# main_16_yobi.net
KiCad netlist of a schematic drawn in EAGLE
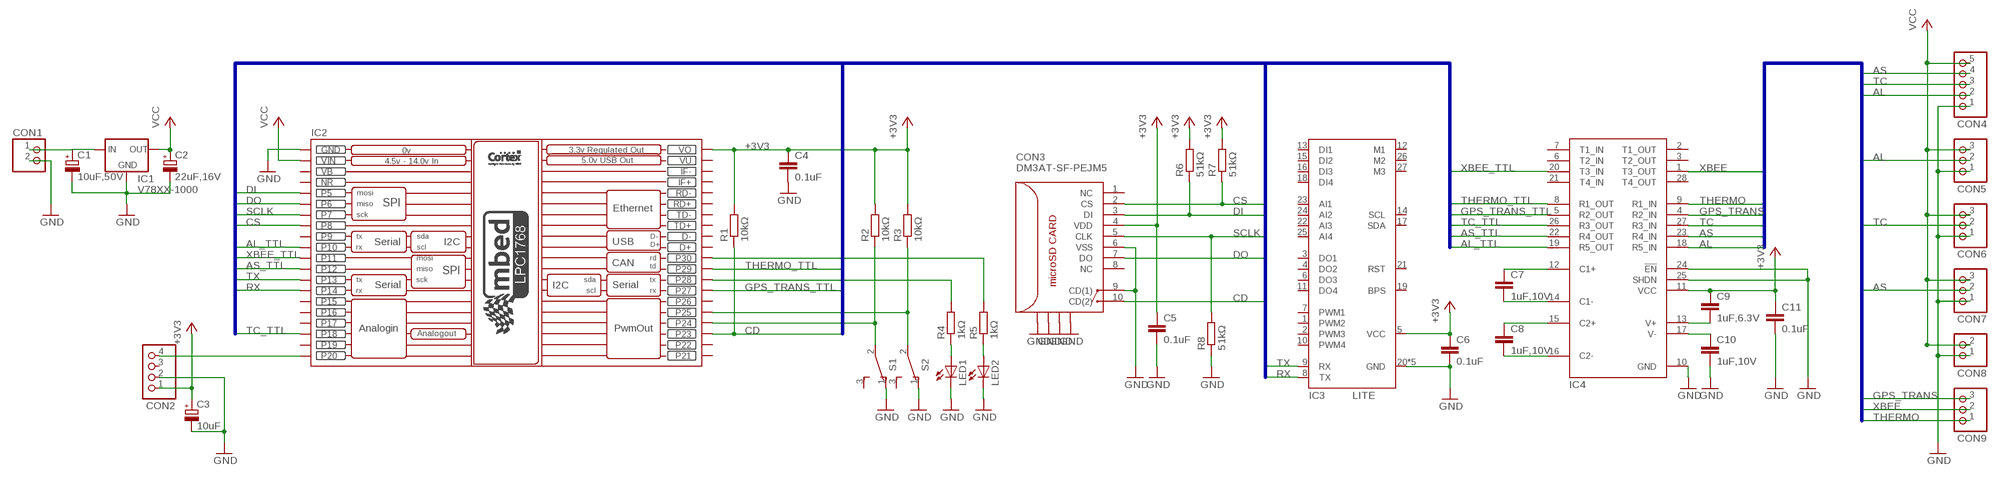
[diagram p0: schematic, sheet 1]

(export (version "E")
  (design (tool "Eeschema 10.0.6"))
  (components
    (comp (ref "C1")
      (value "10uF,50V")
      (footprint "eagle-import:E2,5-5")
      (libsource (lib "eagle-import") (part "CPOL-EUE2.5-5"))
    )
    (comp (ref "C2")
      (value "22uF,16V")
      (footprint "eagle-import:E2,5-6")
      (libsource (lib "eagle-import") (part "CPOL-EUE2.5-6"))
    )
    (comp (ref "C3")
      (value "10uF")
      (footprint "eagle-import:E2,5-5")
      (libsource (lib "eagle-import") (part "CPOL-EUE2.5-5"))
    )
    (comp (ref "C4")
      (value "0.1uF")
      (footprint "eagle-import:C0603")
      (libsource (lib "eagle-import") (part "C-EUC0603"))
    )
    (comp (ref "C5")
      (value "0.1uF")
      (footprint "eagle-import:C0603")
      (libsource (lib "eagle-import") (part "C-EUC0603"))
    )
    (comp (ref "C6")
      (value "0.1uF")
      (footprint "eagle-import:C0603")
      (libsource (lib "eagle-import") (part "C-EUC0603"))
    )
    (comp (ref "C7")
      (value "1uF,10V")
      (footprint "eagle-import:C0603")
      (libsource (lib "eagle-import") (part "C-EUC0603"))
    )
    (comp (ref "C8")
      (value "1uF,10V")
      (footprint "eagle-import:C0603")
      (libsource (lib "eagle-import") (part "C-EUC0603"))
    )
    (comp (ref "C9")
      (value "1uF,6.3V")
      (footprint "eagle-import:C0603")
      (libsource (lib "eagle-import") (part "C-EUC0603"))
    )
    (comp (ref "C10")
      (value "1uF,10V")
      (footprint "eagle-import:C0603")
      (libsource (lib "eagle-import") (part "C-EUC0603"))
    )
    (comp (ref "C11")
      (value "0.1uF")
      (footprint "eagle-import:C0603")
      (libsource (lib "eagle-import") (part "C-EUC0603"))
    )
    (comp (ref "CON1") (value "2") (footprint "eagle-import:2") (libsource (lib "eagle-import") (part "2")))
    (comp (ref "CON2")
      (value "PINHD-1X4")
      (footprint "eagle-import:1X04")
      (libsource (lib "eagle-import") (part "PINHD-1X4"))
    )
    (comp (ref "CON3")
      (value "DM3AT-SF-PEJM5")
      (footprint "eagle-import:DM3AT-SF-PEJM5")
      (libsource (lib "eagle-import") (part "DM3AT-SF-PEJM5"))
    )
    (comp (ref "CON4") (value "5") (footprint "eagle-import:5") (libsource (lib "eagle-import") (part "5")))
    (comp (ref "CON5") (value "3") (footprint "eagle-import:3") (libsource (lib "eagle-import") (part "3")))
    (comp (ref "CON6") (value "3") (footprint "eagle-import:3") (libsource (lib "eagle-import") (part "3")))
    (comp (ref "CON7") (value "3") (footprint "eagle-import:3") (libsource (lib "eagle-import") (part "3")))
    (comp (ref "CON8") (value "2") (footprint "eagle-import:2") (libsource (lib "eagle-import") (part "2")))
    (comp (ref "CON9") (value "3") (footprint "eagle-import:3") (libsource (lib "eagle-import") (part "3")))
    (comp (ref "IC1")
      (value "V78XX-1000")
      (footprint "eagle-import:V78XX-1000")
      (libsource (lib "eagle-import") (part "V78XX-1000"))
    )
    (comp (ref "IC2")
      (value "MBED_NXP_LPC1768")
      (footprint "eagle-import:MBED-KIT")
      (libsource (lib "eagle-import") (part "MBED_NXP_LPC1768"))
    )
    (comp (ref "IC3")
      (value "LITE")
      (footprint "eagle-import:LITE")
      (libsource (lib "eagle-import") (part "LITE"))
    )
    (comp (ref "IC4")
      (value "ADM561")
      (footprint "eagle-import:SO28L")
      (libsource (lib "eagle-import") (part "ADM561"))
    )
    (comp (ref "LED1")
      (value "LED3MM")
      (footprint "eagle-import:LED3MM")
      (libsource (lib "eagle-import") (part "LED3MM"))
    )
    (comp (ref "LED2")
      (value "LED3MM")
      (footprint "eagle-import:LED3MM")
      (libsource (lib "eagle-import") (part "LED3MM"))
    )
    (comp (ref "R1")
      (value "10kΩ")
      (footprint "eagle-import:R0603")
      (libsource (lib "eagle-import") (part "R-EU_R0603"))
    )
    (comp (ref "R2")
      (value "10kΩ")
      (footprint "eagle-import:R0603")
      (libsource (lib "eagle-import") (part "R-EU_R0603"))
    )
    (comp (ref "R3")
      (value "10kΩ")
      (footprint "eagle-import:R0603")
      (libsource (lib "eagle-import") (part "R-EU_R0603"))
    )
    (comp (ref "R4")
      (value "1kΩ")
      (footprint "eagle-import:R0603")
      (libsource (lib "eagle-import") (part "R-EU_R0603"))
    )
    (comp (ref "R5")
      (value "1kΩ")
      (footprint "eagle-import:R0603")
      (libsource (lib "eagle-import") (part "R-EU_R0603"))
    )
    (comp (ref "R6")
      (value "51kΩ")
      (footprint "eagle-import:R0603")
      (libsource (lib "eagle-import") (part "R-EU_R0603"))
    )
    (comp (ref "R7")
      (value "51kΩ")
      (footprint "eagle-import:R0603")
      (libsource (lib "eagle-import") (part "R-EU_R0603"))
    )
    (comp (ref "R8")
      (value "51kΩ")
      (footprint "eagle-import:R0603")
      (libsource (lib "eagle-import") (part "R-EU_R0603"))
    )
    (comp (ref "S1")
      (value "SS-12D00")
      (footprint "eagle-import:SS-12D00")
      (libsource (lib "eagle-import") (part "SS-12D00"))
    )
    (comp (ref "S2")
      (value "SS-12D00")
      (footprint "eagle-import:SS-12D00")
      (libsource (lib "eagle-import") (part "SS-12D00"))
    )
  )
  (nets
    (net (code "1") (name "+3V3") (class "Default")
      (node (ref "C11") (pin "1") (pinfunction "1_1") (pintype "passive"))
      (node (ref "C3") (pin "+") (pinfunction "+_+") (pintype "passive"))
      (node (ref "C4") (pin "1") (pinfunction "1_1") (pintype "passive"))
      (node (ref "C5") (pin "1") (pinfunction "1_1") (pintype "passive"))
      (node (ref "C6") (pin "1") (pinfunction "1_1") (pintype "passive"))
      (node (ref "C9") (pin "1") (pinfunction "1_1") (pintype "passive"))
      (node (ref "CON2") (pin "1") (pinfunction "1_1") (pintype "passive"))
      (node (ref "CON3") (pin "4") (pinfunction "VDD_4") (pintype "power_in"))
      (node (ref "IC2") (pin "VOUT") (pinfunction "VO_VOUT") (pintype "power_in"))
      (node (ref "IC3") (pin "5") (pinfunction "VCC_5") (pintype "power_in"))
      (node (ref "IC4") (pin "11") (pinfunction "VCC_11") (pintype "power_in"))
      (node (ref "R1") (pin "2") (pinfunction "2_2") (pintype "passive"))
      (node (ref "R2") (pin "2") (pinfunction "2_2") (pintype "passive"))
      (node (ref "R3") (pin "2") (pinfunction "2_2") (pintype "passive"))
      (node (ref "R6") (pin "2") (pinfunction "2_2") (pintype "passive"))
      (node (ref "R7") (pin "2") (pinfunction "2_2") (pintype "passive"))
    )
    (net (code "2") (name "/AL") (class "Default")
      (node (ref "CON4") (pin "2") (pinfunction "2_2") (pintype "passive"))
      (node (ref "CON5") (pin "2") (pinfunction "2_2") (pintype "passive"))
      (node (ref "IC4") (pin "18") (pinfunction "R5_IN_18") (pintype "input"))
    )
    (net (code "3") (name "/AL_TTL") (class "Default")
      (node (ref "IC2") (pin "P$10") (pinfunction "P10_P$10") (pintype "bidirectional"))
      (node (ref "IC4") (pin "19") (pinfunction "R5_OUT_19") (pintype "output"))
    )
    (net (code "4") (name "/AS") (class "Default")
      (node (ref "CON4") (pin "4") (pinfunction "4_4") (pintype "passive"))
      (node (ref "CON7") (pin "2") (pinfunction "2_2") (pintype "passive"))
      (node (ref "IC4") (pin "23") (pinfunction "R4_IN_23") (pintype "input"))
    )
    (net (code "5") (name "/AS_TTL") (class "Default")
      (node (ref "IC2") (pin "P$12") (pinfunction "P12_P$12") (pintype "bidirectional"))
      (node (ref "IC4") (pin "22") (pinfunction "R4_OUT_22") (pintype "output"))
    )
    (net (code "6") (name "/CD") (class "Default")
      (node (ref "CON3") (pin "10") (pinfunction "CD(2)_10") (pintype "bidirectional"))
      (node (ref "IC2") (pin "P$23") (pinfunction "P23_P$23") (pintype "bidirectional"))
      (node (ref "R1") (pin "1") (pinfunction "1_1") (pintype "passive"))
    )
    (net (code "7") (name "/CS") (class "Default")
      (node (ref "CON3") (pin "2") (pinfunction "CS_2") (pintype "bidirectional"))
      (node (ref "IC2") (pin "P$8") (pinfunction "P8_P$8") (pintype "bidirectional"))
      (node (ref "R7") (pin "1") (pinfunction "1_1") (pintype "passive"))
    )
    (net (code "8") (name "/DI") (class "Default")
      (node (ref "CON3") (pin "3") (pinfunction "DI_3") (pintype "bidirectional"))
      (node (ref "IC2") (pin "P$5") (pinfunction "P5_P$5") (pintype "bidirectional"))
      (node (ref "R6") (pin "1") (pinfunction "1_1") (pintype "passive"))
    )
    (net (code "9") (name "/DO") (class "Default")
      (node (ref "CON3") (pin "7") (pinfunction "DO_7") (pintype "power_in"))
      (node (ref "IC2") (pin "P$6") (pinfunction "P6_P$6") (pintype "bidirectional"))
    )
    (net (code "10") (name "/GPS_TRANS") (class "Default")
      (node (ref "CON9") (pin "3") (pinfunction "3_3") (pintype "passive"))
      (node (ref "IC4") (pin "4") (pinfunction "R2_IN_4") (pintype "input"))
    )
    (net (code "11") (name "/GPS_TRANS_TTL") (class "Default")
      (node (ref "IC2") (pin "P$27") (pinfunction "P27_P$27") (pintype "bidirectional"))
      (node (ref "IC4") (pin "5") (pinfunction "R2_OUT_5") (pintype "output"))
    )
    (net (code "12") (name "/NR") (class "Default")
      (node (ref "IC2") (pin "NR") (pinfunction "NR_NR") (pintype "power_in"))
    )
    (net (code "13") (name "/RX") (class "Default")
      (node (ref "IC2") (pin "P$14") (pinfunction "P14_P$14") (pintype "bidirectional"))
      (node (ref "IC3") (pin "8") (pinfunction "TX_8") (pintype "output"))
    )
    (net (code "14") (name "/SCLK") (class "Default")
      (node (ref "CON3") (pin "5") (pinfunction "CLK_5") (pintype "bidirectional"))
      (node (ref "IC2") (pin "P$7") (pinfunction "P7_P$7") (pintype "bidirectional"))
      (node (ref "R8") (pin "2") (pinfunction "2_2") (pintype "passive"))
    )
    (net (code "15") (name "/TC") (class "Default")
      (node (ref "CON4") (pin "3") (pinfunction "3_3") (pintype "passive"))
      (node (ref "CON6") (pin "2") (pinfunction "2_2") (pintype "passive"))
      (node (ref "IC4") (pin "27") (pinfunction "R3_IN_27") (pintype "input"))
    )
    (net (code "16") (name "/TC_TTL") (class "Default")
      (node (ref "IC2") (pin "P$18") (pinfunction "P18_P$18") (pintype "bidirectional"))
      (node (ref "IC4") (pin "26") (pinfunction "R3_OUT_26") (pintype "output"))
    )
    (net (code "17") (name "/THERMO") (class "Default")
      (node (ref "CON9") (pin "1") (pinfunction "1_1") (pintype "passive"))
      (node (ref "IC4") (pin "9") (pinfunction "R1_IN_9") (pintype "input"))
    )
    (net (code "18") (name "/THERMO_TTL") (class "Default")
      (node (ref "IC2") (pin "P$29") (pinfunction "P29_P$29") (pintype "bidirectional"))
      (node (ref "IC4") (pin "8") (pinfunction "R1_OUT_8") (pintype "output"))
    )
    (net (code "19") (name "/TX") (class "Default")
      (node (ref "IC2") (pin "P$13") (pinfunction "P13_P$13") (pintype "bidirectional"))
      (node (ref "IC3") (pin "9") (pinfunction "RX_9") (pintype "input"))
    )
    (net (code "20") (name "/VB") (class "Default")
      (node (ref "IC2") (pin "VB") (pinfunction "VB_VB") (pintype "power_in"))
    )
    (net (code "21") (name "/VU") (class "Default")
      (node (ref "IC2") (pin "VU") (pinfunction "VU_VU") (pintype "power_in"))
    )
    (net (code "22") (name "/XBEE") (class "Default")
      (node (ref "CON9") (pin "2") (pinfunction "2_2") (pintype "passive"))
      (node (ref "IC4") (pin "1") (pinfunction "T3_OUT_1") (pintype "output"))
    )
    (net (code "23") (name "/XBEE_TTL") (class "Default")
      (node (ref "IC2") (pin "P$11") (pinfunction "P11_P$11") (pintype "bidirectional"))
      (node (ref "IC4") (pin "20") (pinfunction "T3_IN_20") (pintype "input"))
    )
    (net (code "24") (name "GND") (class "Default")
      (node (ref "C1") (pin "-") (pinfunction "-_-") (pintype "passive"))
      (node (ref "C10") (pin "2") (pinfunction "2_2") (pintype "passive"))
      (node (ref "C11") (pin "2") (pinfunction "2_2") (pintype "passive"))
      (node (ref "C2") (pin "-") (pinfunction "-_-") (pintype "passive"))
      (node (ref "C3") (pin "-") (pinfunction "-_-") (pintype "passive"))
      (node (ref "C4") (pin "2") (pinfunction "2_2") (pintype "passive"))
      (node (ref "C5") (pin "2") (pinfunction "2_2") (pintype "passive"))
      (node (ref "C6") (pin "2") (pinfunction "2_2") (pintype "passive"))
      (node (ref "CON1") (pin "2") (pinfunction "2_2") (pintype "passive"))
      (node (ref "CON2") (pin "2") (pinfunction "2_2") (pintype "passive"))
      (node (ref "CON3") (pin "6") (pinfunction "VSS_6") (pintype "bidirectional"))
      (node (ref "CON3") (pin "9") (pinfunction "CD(1)_9") (pintype "bidirectional"))
      (node (ref "CON3") (pin "P$10") (pinfunction "P$1_P$10") (pintype "passive"))
      (node (ref "CON3") (pin "P$11") (pinfunction "P$2_P$11") (pintype "passive"))
      (node (ref "CON3") (pin "P$12") (pinfunction "P$3_P$12") (pintype "passive"))
      (node (ref "CON3") (pin "P$14") (pinfunction "P$4_P$14") (pintype "passive"))
      (node (ref "CON4") (pin "1") (pinfunction "1_1") (pintype "passive"))
      (node (ref "CON5") (pin "1") (pinfunction "1_1") (pintype "passive"))
      (node (ref "CON6") (pin "1") (pinfunction "1_1") (pintype "passive"))
      (node (ref "CON7") (pin "1") (pinfunction "1_1") (pintype "passive"))
      (node (ref "CON8") (pin "1") (pinfunction "1_1") (pintype "passive"))
      (node (ref "IC1") (pin "2") (pinfunction "GND_2") (pintype "input"))
      (node (ref "IC2") (pin "GND") (pinfunction "GND_GND") (pintype "power_in"))
      (node (ref "IC3") (pin "20") (pinfunction "GND_20") (pintype "power_in"))
      (node (ref "IC3") (pin "28") (pinfunction "GND_28") (pintype "power_in"))
      (node (ref "IC3") (pin "30") (pinfunction "GND_30") (pintype "power_in"))
      (node (ref "IC3") (pin "31") (pinfunction "GND_31") (pintype "power_in"))
      (node (ref "IC3") (pin "32") (pinfunction "GND_32") (pintype "power_in"))
      (node (ref "IC4") (pin "10") (pinfunction "GND_10") (pintype "power_in"))
      (node (ref "IC4") (pin "24") (pinfunction "~{EN}_24") (pintype "input"))
      (node (ref "IC4") (pin "25") (pinfunction "SHDN_25") (pintype "input"))
      (node (ref "LED1") (pin "K") (pinfunction "C_K") (pintype "passive"))
      (node (ref "LED2") (pin "K") (pinfunction "C_K") (pintype "passive"))
      (node (ref "R8") (pin "1") (pinfunction "1_1") (pintype "passive"))
      (node (ref "S1") (pin "1") (pinfunction "O_1") (pintype "passive"))
      (node (ref "S2") (pin "1") (pinfunction "O_1") (pintype "passive"))
    )
    (net (code "25") (name "Net-(IC1-IN)") (class "Default")
      (node (ref "C1") (pin "+") (pinfunction "+_+") (pintype "passive"))
      (node (ref "CON1") (pin "1") (pinfunction "1_1") (pintype "passive"))
      (node (ref "IC1") (pin "1") (pinfunction "IN_1") (pintype "input"))
    )
    (net (code "26") (name "Net-(IC2-P20)") (class "Default")
      (node (ref "CON2") (pin "4") (pinfunction "4_4") (pintype "passive"))
      (node (ref "IC2") (pin "P$20") (pinfunction "P20_P$20") (pintype "bidirectional"))
    )
    (net (code "27") (name "Net-(IC2-P24)") (class "Default")
      (node (ref "IC2") (pin "P$24") (pinfunction "P24_P$24") (pintype "bidirectional"))
      (node (ref "R2") (pin "1") (pinfunction "1_1") (pintype "passive"))
      (node (ref "S1") (pin "2") (pinfunction "P_2") (pintype "passive"))
    )
    (net (code "28") (name "Net-(IC2-P25)") (class "Default")
      (node (ref "IC2") (pin "P$25") (pinfunction "P25_P$25") (pintype "bidirectional"))
      (node (ref "R3") (pin "1") (pinfunction "1_1") (pintype "passive"))
      (node (ref "S2") (pin "2") (pinfunction "P_2") (pintype "passive"))
    )
    (net (code "29") (name "Net-(IC2-P28)") (class "Default")
      (node (ref "IC2") (pin "P$28") (pinfunction "P28_P$28") (pintype "bidirectional"))
      (node (ref "R4") (pin "2") (pinfunction "2_2") (pintype "passive"))
    )
    (net (code "30") (name "Net-(IC2-P30)") (class "Default")
      (node (ref "IC2") (pin "P$30") (pinfunction "P30_P$30") (pintype "bidirectional"))
      (node (ref "R5") (pin "2") (pinfunction "2_2") (pintype "passive"))
    )
    (net (code "31") (name "Net-(IC4-C1+)") (class "Default")
      (node (ref "C7") (pin "1") (pinfunction "1_1") (pintype "passive"))
      (node (ref "IC4") (pin "12") (pinfunction "C1+_12") (pintype "passive"))
    )
    (net (code "32") (name "Net-(IC4-C1-)") (class "Default")
      (node (ref "C7") (pin "2") (pinfunction "2_2") (pintype "passive"))
      (node (ref "IC4") (pin "14") (pinfunction "C1-_14") (pintype "passive"))
    )
    (net (code "33") (name "Net-(IC4-C2+)") (class "Default")
      (node (ref "C8") (pin "1") (pinfunction "1_1") (pintype "passive"))
      (node (ref "IC4") (pin "15") (pinfunction "C2+_15") (pintype "passive"))
    )
    (net (code "34") (name "Net-(IC4-C2-)") (class "Default")
      (node (ref "C8") (pin "2") (pinfunction "2_2") (pintype "passive"))
      (node (ref "IC4") (pin "16") (pinfunction "C2-_16") (pintype "passive"))
    )
    (net (code "35") (name "Net-(IC4-V+)") (class "Default")
      (node (ref "C9") (pin "2") (pinfunction "2_2") (pintype "passive"))
      (node (ref "IC4") (pin "13") (pinfunction "V+_13") (pintype "power_in"))
    )
    (net (code "36") (name "Net-(IC4-V-)") (class "Default")
      (node (ref "C10") (pin "1") (pinfunction "1_1") (pintype "passive"))
      (node (ref "IC4") (pin "17") (pinfunction "V-_17") (pintype "power_in"))
    )
    (net (code "37") (name "Net-(LED1-PadA)") (class "Default")
      (node (ref "LED1") (pin "A") (pinfunction "A_A") (pintype "passive"))
      (node (ref "R4") (pin "1") (pinfunction "1_1") (pintype "passive"))
    )
    (net (code "38") (name "Net-(LED2-PadA)") (class "Default")
      (node (ref "LED2") (pin "A") (pinfunction "A_A") (pintype "passive"))
      (node (ref "R5") (pin "1") (pinfunction "1_1") (pintype "passive"))
    )
    (net (code "39") (name "VCC") (class "Default")
      (node (ref "C2") (pin "+") (pinfunction "+_+") (pintype "passive"))
      (node (ref "CON4") (pin "5") (pinfunction "5_5") (pintype "passive"))
      (node (ref "CON5") (pin "3") (pinfunction "3_3") (pintype "passive"))
      (node (ref "CON6") (pin "3") (pinfunction "3_3") (pintype "passive"))
      (node (ref "CON7") (pin "3") (pinfunction "3_3") (pintype "passive"))
      (node (ref "CON8") (pin "2") (pinfunction "2_2") (pintype "passive"))
      (node (ref "IC1") (pin "3") (pinfunction "OUT_3") (pintype "passive"))
      (node (ref "IC2") (pin "VIN") (pinfunction "VIN_VIN") (pintype "power_in"))
    )
    (net (code "40") (name "unconnected-(CON2-Pad3)") (class "Default")
      (node (ref "CON2") (pin "3") (pinfunction "3_3") (pintype "passive"))
    )
    (net (code "41") (name "unconnected-(CON3-NC-Pad1)") (class "Default")
      (node (ref "CON3") (pin "1") (pinfunction "NC_1") (pintype "no_connect"))
    )
    (net (code "42") (name "unconnected-(CON3-NC-Pad8)") (class "Default")
      (node (ref "CON3") (pin "8") (pinfunction "NC_8") (pintype "no_connect"))
    )
    (net (code "43") (name "unconnected-(IC2-P9-PadP$9)") (class "Default")
      (node (ref "IC2") (pin "P$9") (pinfunction "P9_P$9") (pintype "bidirectional"))
    )
    (net (code "44") (name "unconnected-(IC2-P15-PadP$15)") (class "Default")
      (node (ref "IC2") (pin "P$15") (pinfunction "P15_P$15") (pintype "bidirectional"))
    )
    (net (code "45") (name "unconnected-(IC2-P16-PadP$16)") (class "Default")
      (node (ref "IC2") (pin "P$16") (pinfunction "P16_P$16") (pintype "bidirectional"))
    )
    (net (code "46") (name "unconnected-(IC2-P17-PadP$17)") (class "Default")
      (node (ref "IC2") (pin "P$17") (pinfunction "P17_P$17") (pintype "bidirectional"))
    )
    (net (code "47") (name "unconnected-(IC2-P19-PadP$19)") (class "Default")
      (node (ref "IC2") (pin "P$19") (pinfunction "P19_P$19") (pintype "bidirectional"))
    )
    (net (code "48") (name "unconnected-(IC2-P21-PadP$21)") (class "Default")
      (node (ref "IC2") (pin "P$21") (pinfunction "P21_P$21") (pintype "bidirectional"))
    )
    (net (code "49") (name "unconnected-(IC2-P22-PadP$22)") (class "Default")
      (node (ref "IC2") (pin "P$22") (pinfunction "P22_P$22") (pintype "bidirectional"))
    )
    (net (code "50") (name "unconnected-(IC2-P26-PadP$26)") (class "Default")
      (node (ref "IC2") (pin "P$26") (pinfunction "P26_P$26") (pintype "bidirectional"))
    )
    (net (code "51") (name "unconnected-(IC2-PadD+)") (class "Default")
      (node (ref "IC2") (pin "D+") (pinfunction "D+_D+") (pintype "bidirectional"))
    )
    (net (code "52") (name "unconnected-(IC2-PadD-)") (class "Default")
      (node (ref "IC2") (pin "D-") (pinfunction "D-_D-") (pintype "bidirectional"))
    )
    (net (code "53") (name "unconnected-(IC2-PadIF+)") (class "Default")
      (node (ref "IC2") (pin "IF+") (pinfunction "IF+_IF+") (pintype "bidirectional"))
    )
    (net (code "54") (name "unconnected-(IC2-PadIF-)") (class "Default")
      (node (ref "IC2") (pin "IF-") (pinfunction "IF-_IF-") (pintype "bidirectional"))
    )
    (net (code "55") (name "unconnected-(IC2-PadRD+)") (class "Default")
      (node (ref "IC2") (pin "RD+") (pinfunction "RD+_RD+") (pintype "bidirectional"))
    )
    (net (code "56") (name "unconnected-(IC2-PadRD-)") (class "Default")
      (node (ref "IC2") (pin "RD-") (pinfunction "RD-_RD-") (pintype "bidirectional"))
    )
    (net (code "57") (name "unconnected-(IC2-PadTD+)") (class "Default")
      (node (ref "IC2") (pin "TD+") (pinfunction "TD+_TD+") (pintype "bidirectional"))
    )
    (net (code "58") (name "unconnected-(IC2-PadTD-)") (class "Default")
      (node (ref "IC2") (pin "TD-") (pinfunction "TD-_TD-") (pintype "bidirectional"))
    )
    (net (code "59") (name "unconnected-(IC3-AI1-Pad23)") (class "Default")
      (node (ref "IC3") (pin "23") (pinfunction "AI1_23") (pintype "input"))
    )
    (net (code "60") (name "unconnected-(IC3-AI2-Pad24)") (class "Default")
      (node (ref "IC3") (pin "24") (pinfunction "AI2_24") (pintype "input"))
    )
    (net (code "61") (name "unconnected-(IC3-AI3-Pad22)") (class "Default")
      (node (ref "IC3") (pin "22") (pinfunction "AI3_22") (pintype "input"))
    )
    (net (code "62") (name "unconnected-(IC3-AI4-Pad25)") (class "Default")
      (node (ref "IC3") (pin "25") (pinfunction "AI4_25") (pintype "input"))
    )
    (net (code "63") (name "unconnected-(IC3-BPS-Pad19)") (class "Default")
      (node (ref "IC3") (pin "19") (pinfunction "BPS_19") (pintype "input"))
    )
    (net (code "64") (name "unconnected-(IC3-DI1-Pad13)") (class "Default")
      (node (ref "IC3") (pin "13") (pinfunction "DI1_13") (pintype "input"))
    )
    (net (code "65") (name "unconnected-(IC3-DI2-Pad15)") (class "Default")
      (node (ref "IC3") (pin "15") (pinfunction "DI2_15") (pintype "input"))
    )
    (net (code "66") (name "unconnected-(IC3-DI3-Pad16)") (class "Default")
      (node (ref "IC3") (pin "16") (pinfunction "DI3_16") (pintype "input"))
    )
    (net (code "67") (name "unconnected-(IC3-DI4-Pad18)") (class "Default")
      (node (ref "IC3") (pin "18") (pinfunction "DI4_18") (pintype "input"))
    )
    (net (code "68") (name "unconnected-(IC3-DO1-Pad3)") (class "Default")
      (node (ref "IC3") (pin "3") (pinfunction "DO1_3") (pintype "output"))
    )
    (net (code "69") (name "unconnected-(IC3-DO2-Pad4)") (class "Default")
      (node (ref "IC3") (pin "4") (pinfunction "DO2_4") (pintype "output"))
    )
    (net (code "70") (name "unconnected-(IC3-DO3-Pad6)") (class "Default")
      (node (ref "IC3") (pin "6") (pinfunction "DO3_6") (pintype "output"))
    )
    (net (code "71") (name "unconnected-(IC3-DO4-Pad11)") (class "Default")
      (node (ref "IC3") (pin "11") (pinfunction "DO4_11") (pintype "output"))
    )
    (net (code "72") (name "unconnected-(IC3-M1-Pad12)") (class "Default")
      (node (ref "IC3") (pin "12") (pinfunction "M1_12") (pintype "input"))
    )
    (net (code "73") (name "unconnected-(IC3-M2-Pad26)") (class "Default")
      (node (ref "IC3") (pin "26") (pinfunction "M2_26") (pintype "input"))
    )
    (net (code "74") (name "unconnected-(IC3-M3-Pad27)") (class "Default")
      (node (ref "IC3") (pin "27") (pinfunction "M3_27") (pintype "input"))
    )
    (net (code "75") (name "unconnected-(IC3-PWM1-Pad7)") (class "Default")
      (node (ref "IC3") (pin "7") (pinfunction "PWM1_7") (pintype "output"))
    )
    (net (code "76") (name "unconnected-(IC3-PWM2-Pad1)") (class "Default")
      (node (ref "IC3") (pin "1") (pinfunction "PWM2_1") (pintype "output"))
    )
    (net (code "77") (name "unconnected-(IC3-PWM3-Pad2)") (class "Default")
      (node (ref "IC3") (pin "2") (pinfunction "PWM3_2") (pintype "output"))
    )
    (net (code "78") (name "unconnected-(IC3-PWM4-Pad10)") (class "Default")
      (node (ref "IC3") (pin "10") (pinfunction "PWM4_10") (pintype "output"))
    )
    (net (code "79") (name "unconnected-(IC3-RST-Pad21)") (class "Default")
      (node (ref "IC3") (pin "21") (pinfunction "RST_21") (pintype "input"))
    )
    (net (code "80") (name "unconnected-(IC3-SCL-Pad14)") (class "Default")
      (node (ref "IC3") (pin "14") (pinfunction "SCL_14") (pintype "bidirectional"))
    )
    (net (code "81") (name "unconnected-(IC3-SDA-Pad17)") (class "Default")
      (node (ref "IC3") (pin "17") (pinfunction "SDA_17") (pintype "bidirectional"))
    )
    (net (code "82") (name "unconnected-(IC4-T1_IN-Pad7)") (class "Default")
      (node (ref "IC4") (pin "7") (pinfunction "T1_IN_7") (pintype "input"))
    )
    (net (code "83") (name "unconnected-(IC4-T1_OUT-Pad2)") (class "Default")
      (node (ref "IC4") (pin "2") (pinfunction "T1_OUT_2") (pintype "output"))
    )
    (net (code "84") (name "unconnected-(IC4-T2_IN-Pad6)") (class "Default")
      (node (ref "IC4") (pin "6") (pinfunction "T2_IN_6") (pintype "input"))
    )
    (net (code "85") (name "unconnected-(IC4-T2_OUT-Pad3)") (class "Default")
      (node (ref "IC4") (pin "3") (pinfunction "T2_OUT_3") (pintype "output"))
    )
    (net (code "86") (name "unconnected-(IC4-T4_IN-Pad21)") (class "Default")
      (node (ref "IC4") (pin "21") (pinfunction "T4_IN_21") (pintype "input"))
    )
    (net (code "87") (name "unconnected-(IC4-T4_OUT-Pad28)") (class "Default")
      (node (ref "IC4") (pin "28") (pinfunction "T4_OUT_28") (pintype "output"))
    )
    (net (code "88") (name "unconnected-(S1-S-Pad3)") (class "Default")
      (node (ref "S1") (pin "3") (pinfunction "S_3") (pintype "passive"))
    )
    (net (code "89") (name "unconnected-(S2-S-Pad3)") (class "Default")
      (node (ref "S2") (pin "3") (pinfunction "S_3") (pintype "passive"))
    )
  )
)
